# LDR_Module.net
KiCad netlist of a schematic drawn in Altium Designer
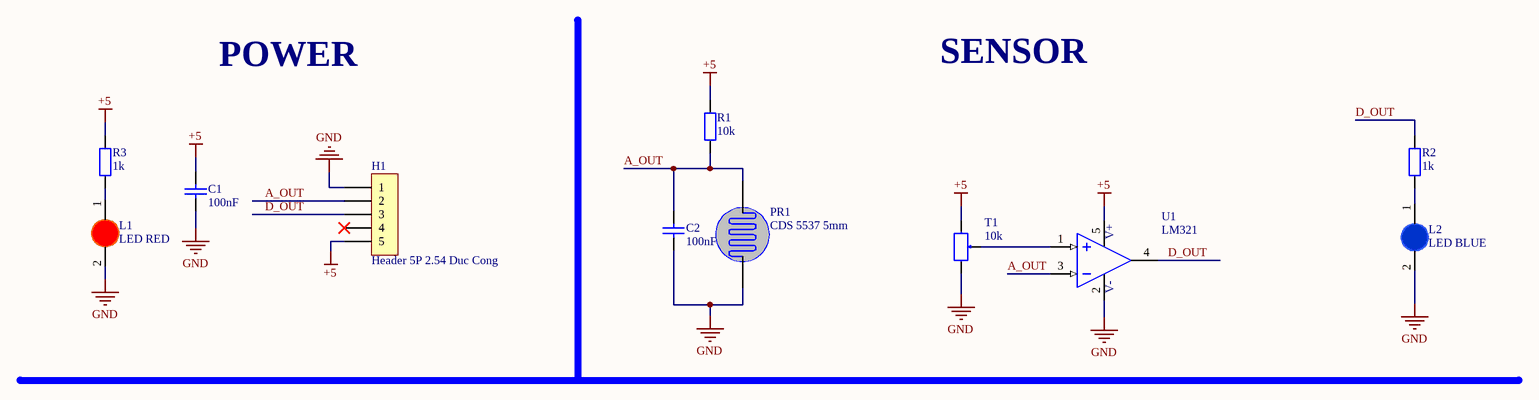
[diagram p0: LDR_Module.SchDoc]

(export (version "E")
  (design (tool "Eeschema 10.0.6"))
  (components
    (comp (ref "C1")
      (value "100nF")
      (footprint "tu 0603")
      (description "Dán")
      (libsource (lib "namnt_Lib") (part "Tu 0603 104 50V 10%"))
    )
    (comp (ref "C2")
      (value "100nF")
      (footprint "tu 0603")
      (description "Dán")
      (libsource (lib "namnt_Lib") (part "Tu 0603 104 50V 10%"))
    )
    (comp (ref "H1")
      (value "Header 5P 2.54 Duc Cong")
      (footprint "Header 5P DC 2.54")
      (description "Cắm")
      (libsource (lib "namnt_Lib") (part "Header 5P 2.54 Duc Cong"))
    )
    (comp (ref "L1")
      (value "LED RED")
      (footprint "LED-0805-Red")
      (description "Dán")
      (libsource (lib "namnt_Lib") (part "LED 0805 Do"))
    )
    (comp (ref "L2")
      (value "LED BLUE")
      (footprint "LED-0805-Blue")
      (description "Dán")
      (libsource (lib "namnt_Lib") (part "LED 0805 Xanh Duong"))
    )
    (comp (ref "PR1")
      (value "CDS 5537 5mm")
      (footprint "Quang Tro")
      (description "Photoresistor")
      (fields (field (name "CREATOR") "Bien Nguyen"))
      (libsource (lib "namnt_Lib") (part "Quang Tro"))
    )
    (comp (ref "R1")
      (value "10k")
      (footprint "tro smd 0603")
      (description "Dán")
      (libsource (lib "namnt_Lib") (part "Tro 0603 1% 10k"))
    )
    (comp (ref "R2")
      (value "1k")
      (footprint "tro smd 0603")
      (description "Dán")
      (libsource (lib "namnt_Lib") (part "Tro 0603 1% 1k"))
    )
    (comp (ref "R3")
      (value "1k")
      (footprint "tro smd 0603")
      (description "Dán")
      (libsource (lib "namnt_Lib") (part "Tro 0603 1% 1k"))
    )
    (comp (ref "T1")
      (value "10k")
      (footprint "Bien Tro Vi Chinh Dung")
      (description "Cắm")
      (libsource (lib "namnt_Lib") (part "Bien Tro Tinh Chinh 10K Dung"))
    )
    (comp (ref "U1")
      (value "LM321")
      (footprint "xlib:sot23-5")
      (description "Opamp")
      (libsource (lib "XLib") (part "LM321"))
    )
  )
  (nets
    (net (code "1") (name "+5") (class "Default")
      (node (ref "C1") (pin "1") (pinfunction "1_1") (pintype "passive"))
      (node (ref "H1") (pin "5") (pinfunction "5_5") (pintype "passive"))
      (node (ref "R1") (pin "2") (pinfunction "2_2") (pintype "passive"))
      (node (ref "R3") (pin "2") (pinfunction "2_2") (pintype "passive"))
      (node (ref "T1") (pin "3") (pinfunction "3_3") (pintype "passive"))
      (node (ref "U1") (pin "5") (pinfunction "V+_5") (pintype "power_in"))
    )
    (net (code "2") (name "/A_OUT") (class "Default")
      (node (ref "C2") (pin "1") (pinfunction "1_1") (pintype "passive"))
      (node (ref "H1") (pin "2") (pinfunction "2_2") (pintype "passive"))
      (node (ref "PR1") (pin "2") (pinfunction "2_2") (pintype "passive"))
      (node (ref "R1") (pin "1") (pinfunction "1_1") (pintype "passive"))
      (node (ref "U1") (pin "3") (pinfunction "IN-_3") (pintype "input"))
    )
    (net (code "3") (name "/D_OUT") (class "Default")
      (node (ref "H1") (pin "3") (pinfunction "3_3") (pintype "passive"))
      (node (ref "R2") (pin "2") (pinfunction "2_2") (pintype "passive"))
      (node (ref "U1") (pin "4") (pinfunction "-V_4") (pintype "passive"))
    )
    (net (code "4") (name "GND") (class "Default")
      (node (ref "C1") (pin "2") (pinfunction "2_2") (pintype "passive"))
      (node (ref "C2") (pin "2") (pinfunction "2_2") (pintype "passive"))
      (node (ref "H1") (pin "1") (pinfunction "1_1") (pintype "passive"))
      (node (ref "L1") (pin "2") (pinfunction "K_2") (pintype "passive"))
      (node (ref "L2") (pin "2") (pinfunction "K_2") (pintype "passive"))
      (node (ref "PR1") (pin "1") (pinfunction "1_1") (pintype "passive"))
      (node (ref "T1") (pin "1") (pinfunction "1_1") (pintype "passive"))
      (node (ref "U1") (pin "2") (pinfunction "V-_2") (pintype "power_in"))
    )
    (net (code "5") (name "Net-(L1-A)") (class "Default")
      (node (ref "L1") (pin "1") (pinfunction "A_1") (pintype "passive"))
      (node (ref "R3") (pin "1") (pinfunction "1_1") (pintype "passive"))
    )
    (net (code "6") (name "Net-(L2-A)") (class "Default")
      (node (ref "L2") (pin "1") (pinfunction "A_1") (pintype "passive"))
      (node (ref "R2") (pin "1") (pinfunction "1_1") (pintype "passive"))
    )
    (net (code "7") (name "Net-(U1-IN+)") (class "Default")
      (node (ref "T1") (pin "2") (pinfunction "2_2") (pintype "passive"))
      (node (ref "U1") (pin "1") (pinfunction "IN+_1") (pintype "input"))
    )
    (net (code "8") (name "unconnected-(H1-Pad4)") (class "Default")
      (node (ref "H1") (pin "4") (pinfunction "4_4") (pintype "passive+no_connect"))
    )
  )
)
